# Photodiode.net
KiCad netlist of a schematic drawn in Altium Designer
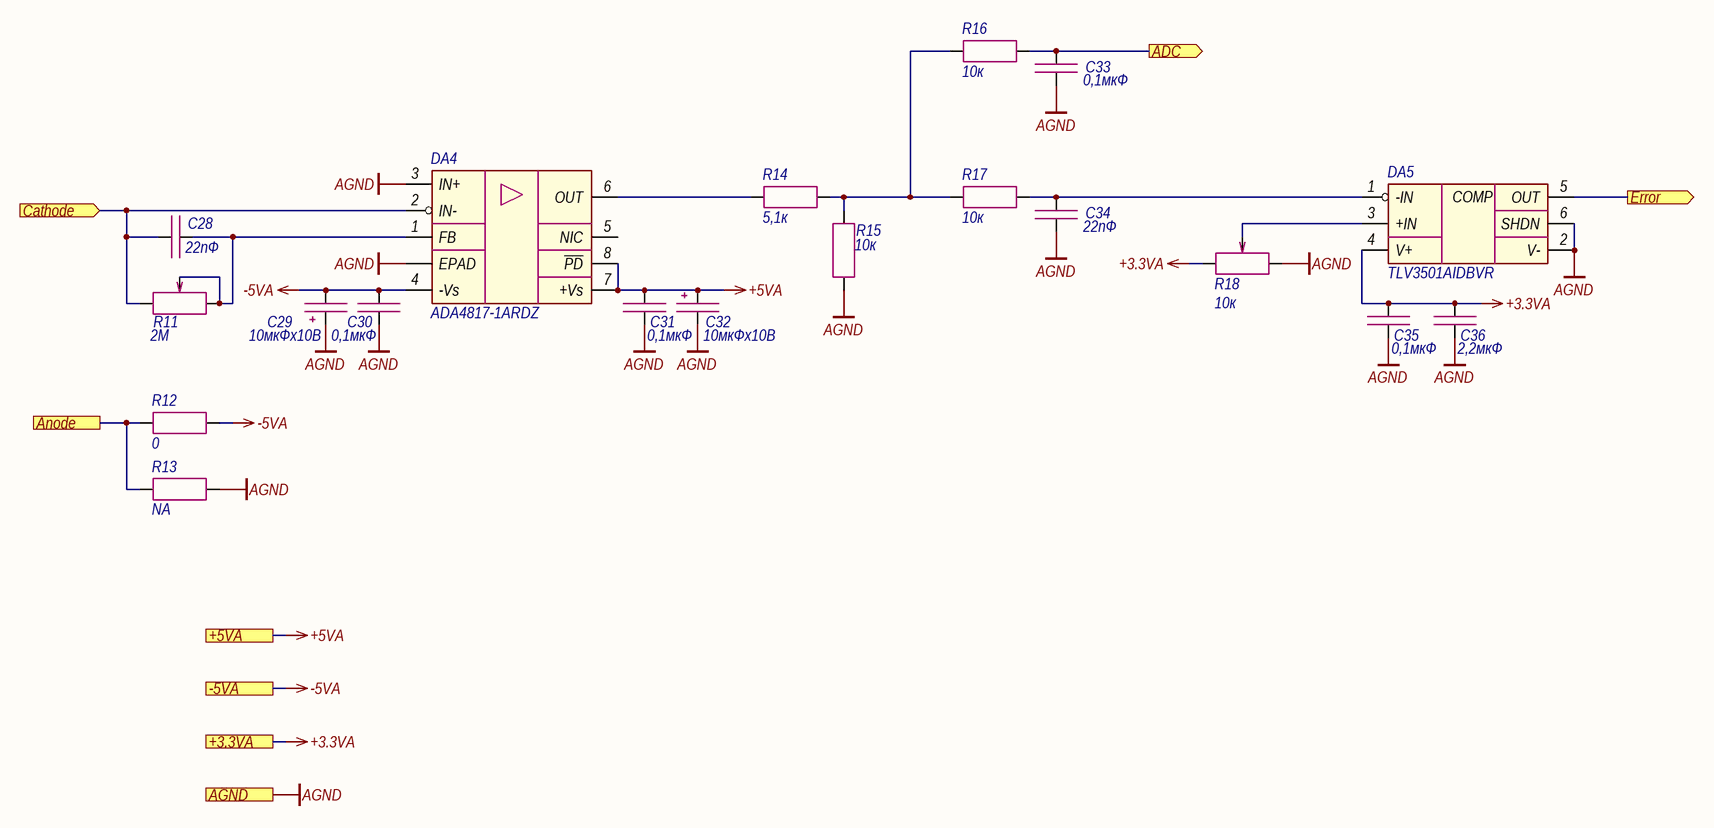
[diagram p0: Photodiode.SchDoc]

(export (version "E")
  (design (tool "Eeschema 10.0.6"))
  (components
    (comp (ref "C28")
      (value "22пФ")
      (footprint "Pcb_library:CAP_0603")
      (fields (field (name "MANUFACTURER") "Murata"))
      (libsource (lib "Schem_library") (part "Capacitor"))
    )
    (comp (ref "C29")
      (value "10мкФх10B")
      (footprint "Pcb_library:CAP_A")
      (libsource (lib "Schem_library") (part "Capacitor_Polar"))
    )
    (comp (ref "C30")
      (value "0,1мкФ")
      (footprint "Pcb_library:CAP_0603")
      (fields (field (name "MANUFACTURER") "Murata"))
      (libsource (lib "Schem_library") (part "Capacitor"))
    )
    (comp (ref "C31")
      (value "0,1мкФ")
      (footprint "Pcb_library:CAP_0603")
      (fields (field (name "MANUFACTURER") "Murata"))
      (libsource (lib "Schem_library") (part "Capacitor"))
    )
    (comp (ref "C32")
      (value "10мкФх10B")
      (footprint "Pcb_library:CAP_A")
      (libsource (lib "Schem_library") (part "Capacitor_Polar"))
    )
    (comp (ref "C33")
      (value "0,1мкФ")
      (footprint "Pcb_library:CAP_0603")
      (fields (field (name "MANUFACTURER") "Murata"))
      (libsource (lib "Schem_library") (part "Capacitor"))
    )
    (comp (ref "C34")
      (value "22пФ")
      (footprint "Pcb_library:CAP_0603")
      (fields (field (name "MANUFACTURER") "Murata"))
      (libsource (lib "Schem_library") (part "Capacitor"))
    )
    (comp (ref "C35")
      (value "0,1мкФ")
      (footprint "Pcb_library:CAP_0603")
      (fields (field (name "MANUFACTURER") "Murata"))
      (libsource (lib "Schem_library") (part "Capacitor"))
    )
    (comp (ref "C36")
      (value "2,2мкФ")
      (footprint "Pcb_library:CAP_0603")
      (fields (field (name "MANUFACTURER") "Murata"))
      (libsource (lib "Schem_library") (part "Capacitor"))
    )
    (comp (ref "DA4")
      (value "ADA4817-1ARDZ")
      (footprint "Pcb_library:SOIC-8 EPAD")
      (fields (field (name "MANUFACTURER") "Analog Devices"))
      (libsource (lib "Schem_library") (part "ADA4817-1ARDZ"))
    )
    (comp (ref "DA5")
      (value "TLV3501AIDBVR")
      (footprint "Pcb_library:SOT-23-6")
      (fields (field (name "MANUFACTURER") "Texas Instruments"))
      (libsource (lib "Schem_library") (part "TLV3501"))
    )
    (comp (ref "R11")
      (value "2М")
      (footprint "Pcb_library:3224W")
      (fields (field (name "MANUFACTURER") "Bourns"))
      (libsource (lib "Schem_library") (part "Resistor_Variable"))
    )
    (comp (ref "R12")
      (value "0")
      (footprint "Pcb_library:RES_0603")
      (fields (field (name "MANUFACTURER") "Yageo"))
      (libsource (lib "Schem_library") (part "Resistor"))
    )
    (comp (ref "R13")
      (value "NA")
      (footprint "Pcb_library:RES_0603")
      (libsource (lib "Schem_library") (part "Resistor"))
    )
    (comp (ref "R14")
      (value "5,1к")
      (footprint "Pcb_library:RES_0603")
      (fields (field (name "MANUFACTURER") "Yageo"))
      (libsource (lib "Schem_library") (part "Resistor"))
    )
    (comp (ref "R15")
      (value "10к")
      (footprint "Pcb_library:RES_0603")
      (fields (field (name "MANUFACTURER") "Yageo"))
      (libsource (lib "Schem_library") (part "Resistor"))
    )
    (comp (ref "R16")
      (value "10к")
      (footprint "Pcb_library:RES_0603")
      (fields (field (name "MANUFACTURER") "Yageo"))
      (libsource (lib "Schem_library") (part "Resistor"))
    )
    (comp (ref "R17")
      (value "10к")
      (footprint "Pcb_library:RES_0603")
      (fields (field (name "MANUFACTURER") "Yageo"))
      (libsource (lib "Schem_library") (part "Resistor"))
    )
    (comp (ref "R18")
      (value "10к")
      (footprint "Pcb_library:3224W")
      (fields (field (name "MANUFACTURER") "Bourns"))
      (libsource (lib "Schem_library") (part "Resistor_Variable"))
    )
  )
  (nets
    (net (code "1") (name "+3.3VA") (class "Default")
      (node (ref "C35") (pin "1") (pinfunction "1_1") (pintype "passive"))
      (node (ref "C36") (pin "1") (pinfunction "1_1") (pintype "passive"))
      (node (ref "DA5") (pin "4") (pinfunction "V+_4") (pintype "passive"))
      (node (ref "R18") (pin "3") (pintype "passive"))
    )
    (net (code "2") (name "+5VA") (class "Default")
      (node (ref "C31") (pin "1") (pinfunction "1_1") (pintype "passive"))
      (node (ref "C32") (pin "1") (pinfunction "1_1") (pintype "passive"))
      (node (ref "DA4") (pin "7") (pinfunction "+Vs_7") (pintype "passive"))
      (node (ref "DA4") (pin "8") (pinfunction "~{PD}_8") (pintype "passive"))
    )
    (net (code "3") (name "-5VA") (class "Default")
      (node (ref "C29") (pin "2") (pinfunction "2_2") (pintype "passive"))
      (node (ref "C30") (pin "1") (pinfunction "1_1") (pintype "passive"))
      (node (ref "DA4") (pin "4") (pinfunction "-Vs_4") (pintype "passive"))
      (node (ref "R12") (pin "1") (pinfunction "1_1") (pintype "passive"))
    )
    (net (code "4") (name "/ADC") (class "Default")
      (node (ref "C33") (pin "1") (pinfunction "1_1") (pintype "passive"))
      (node (ref "R16") (pin "2") (pinfunction "2_2") (pintype "passive"))
    )
    (net (code "5") (name "/Anode") (class "Default")
      (node (ref "R12") (pin "2") (pinfunction "2_2") (pintype "passive"))
      (node (ref "R13") (pin "1") (pinfunction "1_1") (pintype "passive"))
    )
    (net (code "6") (name "/Cathode") (class "Default")
      (node (ref "C28") (pin "2") (pinfunction "2_2") (pintype "passive"))
      (node (ref "DA4") (pin "2") (pinfunction "IN-_2") (pintype "passive"))
      (node (ref "R11") (pin "1") (pintype "passive"))
    )
    (net (code "7") (name "/Error") (class "Default")
      (node (ref "DA5") (pin "5") (pinfunction "OUT_5") (pintype "passive"))
    )
    (net (code "8") (name "AGND") (class "Default")
      (node (ref "C29") (pin "1") (pinfunction "1_1") (pintype "passive"))
      (node (ref "C30") (pin "2") (pinfunction "2_2") (pintype "passive"))
      (node (ref "C31") (pin "2") (pinfunction "2_2") (pintype "passive"))
      (node (ref "C32") (pin "2") (pinfunction "2_2") (pintype "passive"))
      (node (ref "C33") (pin "2") (pinfunction "2_2") (pintype "passive"))
      (node (ref "C34") (pin "2") (pinfunction "2_2") (pintype "passive"))
      (node (ref "C35") (pin "2") (pinfunction "2_2") (pintype "passive"))
      (node (ref "C36") (pin "2") (pinfunction "2_2") (pintype "passive"))
      (node (ref "DA4") (pin "3") (pinfunction "IN+_3") (pintype "passive"))
      (node (ref "DA4") (pin "EPAD") (pinfunction "EPAD_EPAD") (pintype "passive"))
      (node (ref "DA5") (pin "2") (pinfunction "V-_2") (pintype "passive"))
      (node (ref "DA5") (pin "6") (pinfunction "SHDN_6") (pintype "passive"))
      (node (ref "R13") (pin "2") (pinfunction "2_2") (pintype "passive"))
      (node (ref "R15") (pin "2") (pinfunction "2_2") (pintype "passive"))
      (node (ref "R18") (pin "1") (pintype "passive"))
    )
    (net (code "9") (name "Net-(DA4-FB)") (class "Default")
      (node (ref "C28") (pin "1") (pinfunction "1_1") (pintype "passive"))
      (node (ref "DA4") (pin "1") (pinfunction "FB_1") (pintype "passive"))
      (node (ref "R11") (pin "2") (pintype "passive"))
      (node (ref "R11") (pin "3") (pintype "passive"))
    )
    (net (code "10") (name "Net-(DA4-OUT)") (class "Default")
      (node (ref "DA4") (pin "6") (pinfunction "OUT_6") (pintype "passive"))
      (node (ref "R14") (pin "1") (pinfunction "1_1") (pintype "passive"))
    )
    (net (code "11") (name "Net-(DA5-+IN)") (class "Default")
      (node (ref "DA5") (pin "3") (pinfunction "+IN_3") (pintype "passive"))
      (node (ref "R18") (pin "2") (pintype "passive"))
    )
    (net (code "12") (name "Net-(DA5--IN)") (class "Default")
      (node (ref "C34") (pin "1") (pinfunction "1_1") (pintype "passive"))
      (node (ref "DA5") (pin "1") (pinfunction "-IN_1") (pintype "passive"))
      (node (ref "R17") (pin "2") (pinfunction "2_2") (pintype "passive"))
    )
    (net (code "13") (name "Net-(R14-Pad2)") (class "Default")
      (node (ref "R14") (pin "2") (pinfunction "2_2") (pintype "passive"))
      (node (ref "R15") (pin "1") (pinfunction "1_1") (pintype "passive"))
      (node (ref "R16") (pin "1") (pinfunction "1_1") (pintype "passive"))
      (node (ref "R17") (pin "1") (pinfunction "1_1") (pintype "passive"))
    )
    (net (code "14") (name "unconnected-(DA4-NIC-Pad5)") (class "Default")
      (node (ref "DA4") (pin "5") (pinfunction "NIC_5") (pintype "passive"))
    )
  )
)
